# preamp_chanel1_bright.net
KiCad netlist of a schematic drawn in Altium Designer
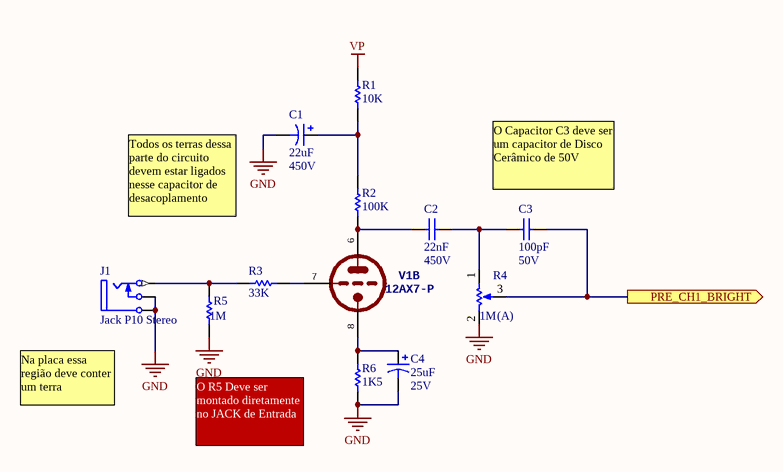
[diagram p0: preamp_chanel1_bright.SchDoc]

(export (version "E")
  (design (tool "Eeschema 10.0.6"))
  (components
    (comp (ref "C1")
      (value "22uF")
      (footprint "capacitors:RAD-POL-7.6-15")
      (description "Polarized Capacitor (Axial)")
      (fields
        (field (name "VOLTAGE") "450V")
        (field (name "Comment") "Cap Pol Rad")
        (field (name "PUBLISHER") "Altium Limited")
      )
      (libsource (lib "capacitors") (part "Cap Pol Rad"))
    )
    (comp (ref "C2")
      (value "22nF")
      (footprint "ORANGE-DROP-100nF")
      (description "Capacitor")
      (fields
        (field (name "VOLTAGE") "450V")
        (field (name "Comment") "Polyester Film")
        (field (name "PUBLISHER") "Altium Limited")
      )
      (libsource (lib "capacitors") (part "Cap-PFilm"))
    )
    (comp (ref "C3")
      (value "100pF")
      (footprint "Miscellaneous Devices:RAD-0.2")
      (description "Capacitor")
      (fields
        (field (name "VOLTAGE") "50V")
        (field (name "Comment") "Ceramic Cap")
        (field (name "PUBLISHER") "Altium Limited")
      )
      (libsource (lib "capacitors") (part "Cap-Ceramic-Small"))
    )
    (comp (ref "C4")
      (value "25uF")
      (footprint "AXIAL-POL-30mm")
      (description "Polarized Capacitor Axial")
      (fields
        (field (name "VOLTAGE") "25V")
        (field (name "Comment") "Cap Pol Axial")
        (field (name "PUBLISHER") "Whitesheep Amps")
      )
      (libsource (lib "capacitors") (part "Cap Pol Axial"))
    )
    (comp (ref "J1")
      (value "Jack P10 Stereo")
      (footprint "JACK-STEREO-3PAD")
      (description "Jack Socket, 1/4\" [6.5mm], Thru-Hole, Vertical, 2-Conductor with Tip closed")
      (fields (field (name "PUBLISHER") "Altium Limited"))
      (libsource (lib "jacks") (part "Jack P10 Stereo"))
    )
    (comp (ref "R1")
      (value "10K")
      (footprint "AXIAL-0.6")
      (description "Semiconductor Resistor")
      (fields
        (field (name "POWER") "1/2W")
        (field (name "Comment") "Metal Film Resistor 1/2W")
        (field (name "PUBLISHER") "Whitesheep Amps")
      )
      (libsource (lib "resistors") (part "Res Metal Film 1/2W"))
    )
    (comp (ref "R2")
      (value "100K")
      (footprint "AXIAL-0.6")
      (description "Semiconductor Resistor")
      (fields
        (field (name "POWER") "1/2W")
        (field (name "Comment") "Metal Film Resistor 1/2W")
        (field (name "PUBLISHER") "Whitesheep Amps")
      )
      (libsource (lib "resistors") (part "Res Metal Film 1/2W"))
    )
    (comp (ref "R3")
      (value "33K")
      (footprint "AXIAL-0.6")
      (description "Semiconductor Resistor")
      (fields
        (field (name "POWER") "1/2W")
        (field (name "Comment") "Metal Film Resistor 1/2W")
        (field (name "PUBLISHER") "Whitesheep Amps")
      )
      (libsource (lib "resistors") (part "Res Metal Film 1/2W"))
    )
    (comp (ref "R4")
      (value "1M")
      (footprint "pot_alpha - 2.54mm")
      (description "Potentiometer")
      (fields
        (field (name "TYPE") "(A)")
        (field (name "Comment") "ALPHA Potentiometer")
        (field (name "PUBLISHER") "Altium Limited")
      )
      (libsource (lib "potentiometers") (part "alpha-pot"))
    )
    (comp (ref "R5")
      (value "1M")
      (footprint "AXIAL-0.6")
      (description "Semiconductor Resistor")
      (fields
        (field (name "POWER") "1/2W")
        (field (name "Comment") "Metal Film Resistor 1/2W")
        (field (name "PUBLISHER") "Whitesheep Amps")
      )
      (libsource (lib "resistors") (part "Res Metal Film 1/2W"))
    )
    (comp (ref "R6")
      (value "1K5")
      (footprint "AXIAL-0.6")
      (description "Semiconductor Resistor")
      (fields
        (field (name "POWER") "1/2W")
        (field (name "Comment") "Metal Film Resistor 1/2W")
        (field (name "PUBLISHER") "Whitesheep Amps")
      )
      (libsource (lib "resistors") (part "Res Metal Film 1/2W"))
    )
    (comp (ref "V1")
      (value "12AX7-P")
      (footprint "NOVAL")
      (libsource (lib "eagle_tubes_v6") (part "12AX7-P"))
    )
  )
  (nets
    (net (code "1") (name "/PRE_CH1_BRIGHT") (class "Default")
      (node (ref "C3") (pin "2") (pinfunction "2_2") (pintype "passive"))
      (node (ref "R4") (pin "3") (pinfunction "TAP_3") (pintype "passive"))
    )
    (net (code "2") (name "GND") (class "Default")
      (node (ref "C1") (pin "2") (pinfunction "2_2") (pintype "passive"))
      (node (ref "C4") (pin "2") (pinfunction "2_2") (pintype "passive"))
      (node (ref "J1") (pin "2") (pinfunction "TN_2") (pintype "passive"))
      (node (ref "J1") (pin "5") (pinfunction "S_5") (pintype "power_in"))
      (node (ref "R4") (pin "2") (pinfunction "BOT_2") (pintype "passive"))
      (node (ref "R5") (pin "1") (pinfunction "1_1") (pintype "passive"))
      (node (ref "R6") (pin "1") (pinfunction "1_1") (pintype "passive"))
    )
    (net (code "3") (name "Net-(C1-Pad1)") (class "Default")
      (node (ref "C1") (pin "1") (pinfunction "1_1") (pintype "passive"))
      (node (ref "R1") (pin "1") (pinfunction "1_1") (pintype "passive"))
      (node (ref "R2") (pin "2") (pinfunction "2_2") (pintype "passive"))
    )
    (net (code "4") (name "Net-(J1-T)") (class "Default")
      (node (ref "J1") (pin "1") (pinfunction "T_1") (pintype "output"))
      (node (ref "R3") (pin "2") (pinfunction "2_2") (pintype "passive"))
      (node (ref "R5") (pin "2") (pinfunction "2_2") (pintype "passive"))
    )
    (net (code "5") (name "Net-(R4-TOP)") (class "Default")
      (node (ref "C2") (pin "2") (pinfunction "2_2") (pintype "passive"))
      (node (ref "C3") (pin "1") (pinfunction "1_1") (pintype "passive"))
      (node (ref "R4") (pin "1") (pinfunction "TOP_1") (pintype "passive"))
    )
    (net (code "6") (name "Net-(V1B-TA)") (class "Default")
      (node (ref "C2") (pin "1") (pinfunction "1_1") (pintype "passive"))
      (node (ref "R2") (pin "1") (pinfunction "1_1") (pintype "passive"))
      (node (ref "V1") (pin "6") (pinfunction "TA_6") (pintype "passive"))
    )
    (net (code "7") (name "Net-(V1B-TG)") (class "Default")
      (node (ref "R3") (pin "1") (pinfunction "1_1") (pintype "passive"))
      (node (ref "V1") (pin "7") (pinfunction "TG_7") (pintype "passive"))
    )
    (net (code "8") (name "Net-(V1B-TK)") (class "Default")
      (node (ref "C4") (pin "1") (pinfunction "1_1") (pintype "passive"))
      (node (ref "R6") (pin "2") (pinfunction "2_2") (pintype "passive"))
      (node (ref "V1") (pin "8") (pinfunction "TK_8") (pintype "passive"))
    )
    (net (code "9") (name "VP") (class "Default")
      (node (ref "R1") (pin "2") (pinfunction "2_2") (pintype "passive"))
    )
  )
)
